# Navigation.net
KiCad netlist of a schematic drawn in Altium Designer
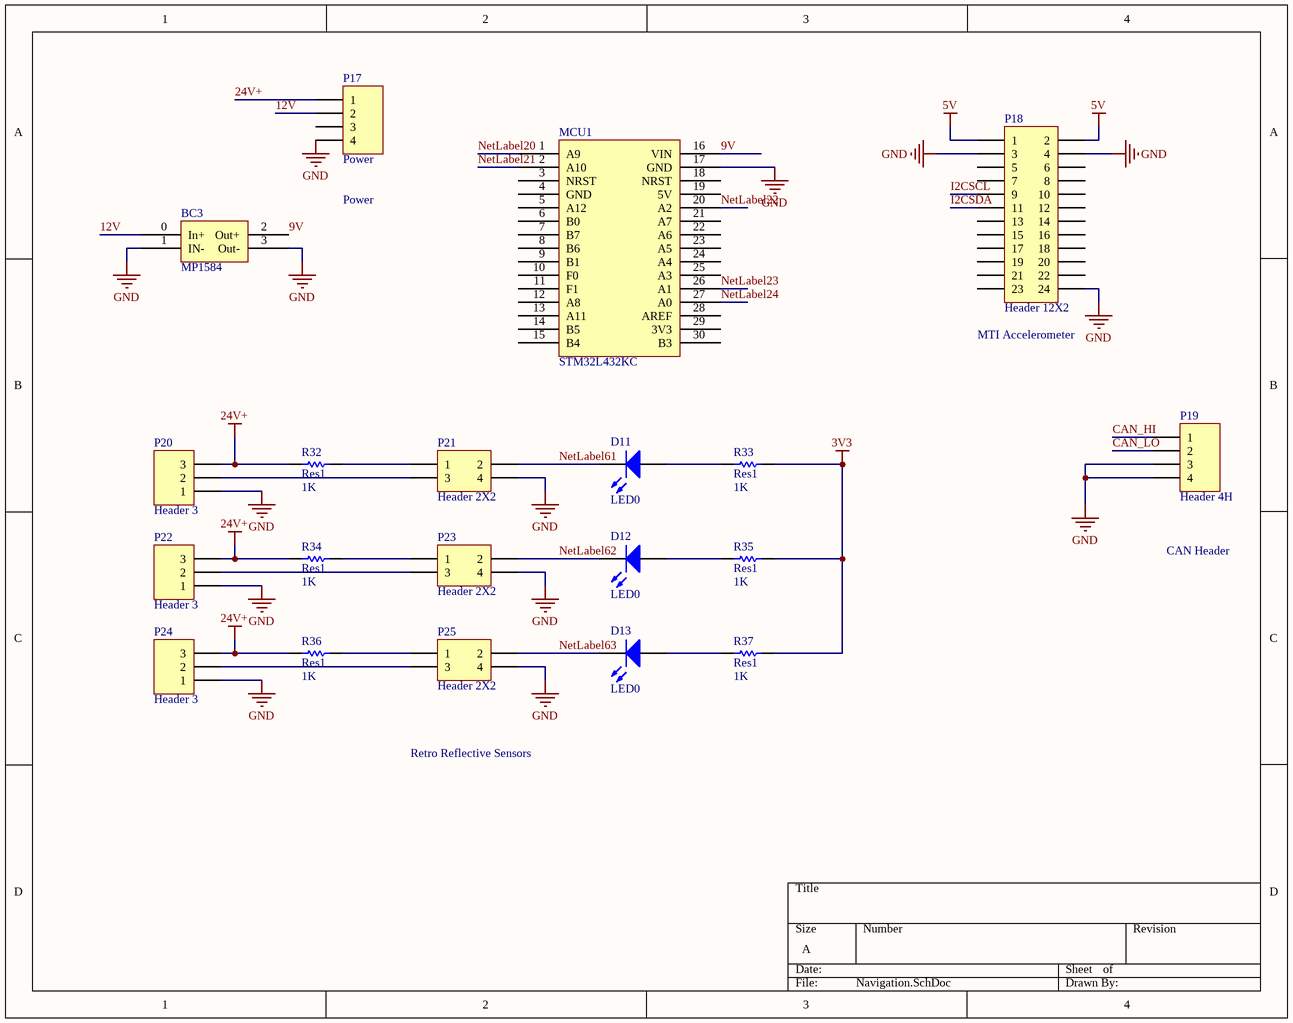
[diagram p0: Navigation.SchDoc]

(export (version "E")
  (design (tool "Eeschema 10.0.6"))
  (components
    (comp (ref "BC3") (value "MP1584") (libsource (lib "Pod3") (part "MP1584")))
    (comp (ref "D11")
      (value "LED0")
      (footprint "LED-0")
      (description "Typical INFRARED GaAs LED")
      (fields (field (name "PUBLISHER") "Altium Limited"))
      (libsource (lib "Miscellaneous Devices") (part "LED0"))
    )
    (comp (ref "D12")
      (value "LED0")
      (footprint "LED-0")
      (description "Typical INFRARED GaAs LED")
      (fields (field (name "PUBLISHER") "Altium Limited"))
      (libsource (lib "Miscellaneous Devices") (part "LED0"))
    )
    (comp (ref "D13")
      (value "LED0")
      (footprint "LED-0")
      (description "Typical INFRARED GaAs LED")
      (fields (field (name "PUBLISHER") "Altium Limited"))
      (libsource (lib "Miscellaneous Devices") (part "LED0"))
    )
    (comp (ref "MCU1") (value "STM32L432KC") (libsource (lib "Pod3") (part "STMF303K8")))
    (comp (ref "P17")
      (value "Power")
      (footprint "HDR1X4")
      (description "Header, 4-Pin")
      (fields (field (name "PUBLISHER") "Altium Limited"))
      (libsource (lib "Miscellaneous Connectors") (part "Header 4"))
    )
    (comp (ref "P18")
      (value "Header 12X2")
      (footprint "HDR2X12")
      (description "Header, 12-Pin, Dual row")
      (fields (field (name "PUBLISHER") "Altium Limited"))
      (libsource (lib "Miscellaneous Connectors") (part "Header 12X2"))
    )
    (comp (ref "P19")
      (value "Header 4H")
      (footprint "HDR1X4H")
      (description "Header, 4-Pin, Right Angle")
      (fields (field (name "PUBLISHER") "Altium Limited"))
      (libsource (lib "Miscellaneous Connectors") (part "Header 4H"))
    )
    (comp (ref "P20")
      (value "Header 3")
      (footprint "HDR1X3")
      (description "Header, 3-Pin")
      (fields (field (name "PUBLISHER") "Altium Limited"))
      (libsource (lib "Miscellaneous Connectors") (part "Header 3"))
    )
    (comp (ref "P21")
      (value "Header 2X2")
      (footprint "HDR2X2")
      (description "Header, 2-Pin, Dual row")
      (fields (field (name "PUBLISHER") "Altium Limited"))
      (libsource (lib "Miscellaneous Connectors") (part "Header 2X2"))
    )
    (comp (ref "P22")
      (value "Header 3")
      (footprint "HDR1X3")
      (description "Header, 3-Pin")
      (fields (field (name "PUBLISHER") "Altium Limited"))
      (libsource (lib "Miscellaneous Connectors") (part "Header 3"))
    )
    (comp (ref "P23")
      (value "Header 2X2")
      (footprint "HDR2X2")
      (description "Header, 2-Pin, Dual row")
      (fields (field (name "PUBLISHER") "Altium Limited"))
      (libsource (lib "Miscellaneous Connectors") (part "Header 2X2"))
    )
    (comp (ref "P24")
      (value "Header 3")
      (footprint "HDR1X3")
      (description "Header, 3-Pin")
      (fields (field (name "PUBLISHER") "Altium Limited"))
      (libsource (lib "Miscellaneous Connectors") (part "Header 3"))
    )
    (comp (ref "P25")
      (value "Header 2X2")
      (footprint "HDR2X2")
      (description "Header, 2-Pin, Dual row")
      (fields (field (name "PUBLISHER") "Altium Limited"))
      (libsource (lib "Miscellaneous Connectors") (part "Header 2X2"))
    )
    (comp (ref "R32")
      (value "Res1")
      (footprint "AXIAL-0.3")
      (description "Resistor")
      (fields (field (name "ALTIUM_VALUE") "1K") (field (name "PUBLISHER") "Altium Limited"))
      (libsource (lib "Miscellaneous Devices") (part "Res1"))
    )
    (comp (ref "R33")
      (value "Res1")
      (footprint "AXIAL-0.3")
      (description "Resistor")
      (fields (field (name "ALTIUM_VALUE") "1K") (field (name "PUBLISHER") "Altium Limited"))
      (libsource (lib "Miscellaneous Devices") (part "Res1"))
    )
    (comp (ref "R34")
      (value "Res1")
      (footprint "AXIAL-0.3")
      (description "Resistor")
      (fields (field (name "ALTIUM_VALUE") "1K") (field (name "PUBLISHER") "Altium Limited"))
      (libsource (lib "Miscellaneous Devices") (part "Res1"))
    )
    (comp (ref "R35")
      (value "Res1")
      (footprint "AXIAL-0.3")
      (description "Resistor")
      (fields (field (name "ALTIUM_VALUE") "1K") (field (name "PUBLISHER") "Altium Limited"))
      (libsource (lib "Miscellaneous Devices") (part "Res1"))
    )
    (comp (ref "R36")
      (value "Res1")
      (footprint "AXIAL-0.3")
      (description "Resistor")
      (fields (field (name "ALTIUM_VALUE") "1K") (field (name "PUBLISHER") "Altium Limited"))
      (libsource (lib "Miscellaneous Devices") (part "Res1"))
    )
    (comp (ref "R37")
      (value "Res1")
      (footprint "AXIAL-0.3")
      (description "Resistor")
      (fields (field (name "ALTIUM_VALUE") "1K") (field (name "PUBLISHER") "Altium Limited"))
      (libsource (lib "Miscellaneous Devices") (part "Res1"))
    )
  )
  (nets
    (net (code "1") (name "/9V") (class "Default")
      (node (ref "BC3") (pin "2") (pinfunction "Out+_2") (pintype "passive"))
      (node (ref "MCU1") (pin "16") (pinfunction "VIN_16") (pintype "passive"))
    )
    (net (code "2") (name "/12V") (class "Default")
      (node (ref "BC3") (pin "0") (pinfunction "In+_0") (pintype "passive"))
      (node (ref "P17") (pin "2") (pinfunction "2_2") (pintype "passive"))
    )
    (net (code "3") (name "/CAN_HI") (class "Default")
      (node (ref "P19") (pin "1") (pinfunction "1_1") (pintype "passive"))
    )
    (net (code "4") (name "/CAN_LO") (class "Default")
      (node (ref "P19") (pin "2") (pinfunction "2_2") (pintype "passive"))
    )
    (net (code "5") (name "/I2CSCL") (class "Default")
      (node (ref "P18") (pin "9") (pinfunction "9_9") (pintype "passive"))
    )
    (net (code "6") (name "/I2CSDA") (class "Default")
      (node (ref "P18") (pin "11") (pinfunction "11_11") (pintype "passive"))
    )
    (net (code "7") (name "/NetLabel20") (class "Default")
      (node (ref "MCU1") (pin "1") (pinfunction "A9_1") (pintype "passive"))
    )
    (net (code "8") (name "/NetLabel21") (class "Default")
      (node (ref "MCU1") (pin "2") (pinfunction "A10_2") (pintype "passive"))
    )
    (net (code "9") (name "/NetLabel22") (class "Default")
      (node (ref "MCU1") (pin "20") (pinfunction "A2_20") (pintype "passive"))
    )
    (net (code "10") (name "/NetLabel23") (class "Default")
      (node (ref "MCU1") (pin "26") (pinfunction "A1_26") (pintype "passive"))
    )
    (net (code "11") (name "/NetLabel24") (class "Default")
      (node (ref "MCU1") (pin "27") (pinfunction "A0_27") (pintype "passive"))
    )
    (net (code "12") (name "/NetLabel61") (class "Default")
      (node (ref "D11") (pin "2") (pinfunction "K_2") (pintype "passive"))
      (node (ref "P21") (pin "2") (pinfunction "2_2") (pintype "passive"))
    )
    (net (code "13") (name "/NetLabel62") (class "Default")
      (node (ref "D12") (pin "2") (pinfunction "K_2") (pintype "passive"))
      (node (ref "P23") (pin "2") (pinfunction "2_2") (pintype "passive"))
    )
    (net (code "14") (name "/NetLabel63") (class "Default")
      (node (ref "D13") (pin "2") (pinfunction "K_2") (pintype "passive"))
      (node (ref "P25") (pin "2") (pinfunction "2_2") (pintype "passive"))
    )
    (net (code "15") (name "3V3") (class "Default")
      (node (ref "R33") (pin "2") (pinfunction "2_2") (pintype "passive"))
      (node (ref "R35") (pin "2") (pinfunction "2_2") (pintype "passive"))
      (node (ref "R37") (pin "2") (pinfunction "2_2") (pintype "passive"))
    )
    (net (code "16") (name "5V") (class "Default")
      (node (ref "P18") (pin "1") (pinfunction "1_1") (pintype "passive"))
      (node (ref "P18") (pin "2") (pinfunction "2_2") (pintype "passive"))
    )
    (net (code "17") (name "24V+") (class "Default")
      (node (ref "P17") (pin "1") (pinfunction "1_1") (pintype "passive"))
      (node (ref "P20") (pin "3") (pinfunction "3_3") (pintype "passive"))
      (node (ref "P22") (pin "3") (pinfunction "3_3") (pintype "passive"))
      (node (ref "P24") (pin "3") (pinfunction "3_3") (pintype "passive"))
      (node (ref "R32") (pin "1") (pinfunction "1_1") (pintype "passive"))
      (node (ref "R34") (pin "1") (pinfunction "1_1") (pintype "passive"))
      (node (ref "R36") (pin "1") (pinfunction "1_1") (pintype "passive"))
    )
    (net (code "18") (name "GND") (class "Default")
      (node (ref "BC3") (pin "1") (pinfunction "IN-_1") (pintype "passive"))
      (node (ref "BC3") (pin "3") (pinfunction "Out-_3") (pintype "passive"))
      (node (ref "MCU1") (pin "17") (pinfunction "GND_17") (pintype "passive"))
      (node (ref "P17") (pin "4") (pinfunction "4_4") (pintype "passive"))
      (node (ref "P18") (pin "24") (pinfunction "24_24") (pintype "passive"))
      (node (ref "P18") (pin "3") (pinfunction "3_3") (pintype "passive"))
      (node (ref "P18") (pin "4") (pinfunction "4_4") (pintype "passive"))
      (node (ref "P19") (pin "3") (pinfunction "3_3") (pintype "passive"))
      (node (ref "P19") (pin "4") (pinfunction "4_4") (pintype "passive"))
      (node (ref "P20") (pin "1") (pinfunction "1_1") (pintype "passive"))
      (node (ref "P21") (pin "4") (pinfunction "4_4") (pintype "passive"))
      (node (ref "P22") (pin "1") (pinfunction "1_1") (pintype "passive"))
      (node (ref "P23") (pin "4") (pinfunction "4_4") (pintype "passive"))
      (node (ref "P24") (pin "1") (pinfunction "1_1") (pintype "passive"))
      (node (ref "P25") (pin "4") (pinfunction "4_4") (pintype "passive"))
    )
    (net (code "19") (name "Net-(D11-A)") (class "Default")
      (node (ref "D11") (pin "1") (pinfunction "A_1") (pintype "passive"))
      (node (ref "R33") (pin "1") (pinfunction "1_1") (pintype "passive"))
    )
    (net (code "20") (name "Net-(D12-A)") (class "Default")
      (node (ref "D12") (pin "1") (pinfunction "A_1") (pintype "passive"))
      (node (ref "R35") (pin "1") (pinfunction "1_1") (pintype "passive"))
    )
    (net (code "21") (name "Net-(D13-A)") (class "Default")
      (node (ref "D13") (pin "1") (pinfunction "A_1") (pintype "passive"))
      (node (ref "R37") (pin "1") (pinfunction "1_1") (pintype "passive"))
    )
    (net (code "22") (name "Net-(P20-Pad2)") (class "Default")
      (node (ref "P20") (pin "2") (pinfunction "2_2") (pintype "passive"))
      (node (ref "P21") (pin "3") (pinfunction "3_3") (pintype "passive"))
    )
    (net (code "23") (name "Net-(P21-Pad1)") (class "Default")
      (node (ref "P21") (pin "1") (pinfunction "1_1") (pintype "passive"))
      (node (ref "R32") (pin "2") (pinfunction "2_2") (pintype "passive"))
    )
    (net (code "24") (name "Net-(P22-Pad2)") (class "Default")
      (node (ref "P22") (pin "2") (pinfunction "2_2") (pintype "passive"))
      (node (ref "P23") (pin "3") (pinfunction "3_3") (pintype "passive"))
    )
    (net (code "25") (name "Net-(P23-Pad1)") (class "Default")
      (node (ref "P23") (pin "1") (pinfunction "1_1") (pintype "passive"))
      (node (ref "R34") (pin "2") (pinfunction "2_2") (pintype "passive"))
    )
    (net (code "26") (name "Net-(P24-Pad2)") (class "Default")
      (node (ref "P24") (pin "2") (pinfunction "2_2") (pintype "passive"))
      (node (ref "P25") (pin "3") (pinfunction "3_3") (pintype "passive"))
    )
    (net (code "27") (name "Net-(P25-Pad1)") (class "Default")
      (node (ref "P25") (pin "1") (pinfunction "1_1") (pintype "passive"))
      (node (ref "R36") (pin "2") (pinfunction "2_2") (pintype "passive"))
    )
    (net (code "28") (name "unconnected-(MCU1-3V3-Pad29)") (class "Default")
      (node (ref "MCU1") (pin "29") (pinfunction "3V3_29") (pintype "passive"))
    )
    (net (code "29") (name "unconnected-(MCU1-5V-Pad19)") (class "Default")
      (node (ref "MCU1") (pin "19") (pinfunction "5V_19") (pintype "passive"))
    )
    (net (code "30") (name "unconnected-(MCU1-A3-Pad25)") (class "Default")
      (node (ref "MCU1") (pin "25") (pinfunction "A3_25") (pintype "passive"))
    )
    (net (code "31") (name "unconnected-(MCU1-A4-Pad24)") (class "Default")
      (node (ref "MCU1") (pin "24") (pinfunction "A4_24") (pintype "passive"))
    )
    (net (code "32") (name "unconnected-(MCU1-A5-Pad23)") (class "Default")
      (node (ref "MCU1") (pin "23") (pinfunction "A5_23") (pintype "passive"))
    )
    (net (code "33") (name "unconnected-(MCU1-A6-Pad22)") (class "Default")
      (node (ref "MCU1") (pin "22") (pinfunction "A6_22") (pintype "passive"))
    )
    (net (code "34") (name "unconnected-(MCU1-A7-Pad21)") (class "Default")
      (node (ref "MCU1") (pin "21") (pinfunction "A7_21") (pintype "passive"))
    )
    (net (code "35") (name "unconnected-(MCU1-A8-Pad12)") (class "Default")
      (node (ref "MCU1") (pin "12") (pinfunction "A8_12") (pintype "passive"))
    )
    (net (code "36") (name "unconnected-(MCU1-A11-Pad13)") (class "Default")
      (node (ref "MCU1") (pin "13") (pinfunction "A11_13") (pintype "passive"))
    )
    (net (code "37") (name "unconnected-(MCU1-A12-Pad5)") (class "Default")
      (node (ref "MCU1") (pin "5") (pinfunction "A12_5") (pintype "passive"))
    )
    (net (code "38") (name "unconnected-(MCU1-AREF-Pad28)") (class "Default")
      (node (ref "MCU1") (pin "28") (pinfunction "AREF_28") (pintype "passive"))
    )
    (net (code "39") (name "unconnected-(MCU1-B0-Pad6)") (class "Default")
      (node (ref "MCU1") (pin "6") (pinfunction "B0_6") (pintype "passive"))
    )
    (net (code "40") (name "unconnected-(MCU1-B1-Pad9)") (class "Default")
      (node (ref "MCU1") (pin "9") (pinfunction "B1_9") (pintype "passive"))
    )
    (net (code "41") (name "unconnected-(MCU1-B3-Pad30)") (class "Default")
      (node (ref "MCU1") (pin "30") (pinfunction "B3_30") (pintype "passive"))
    )
    (net (code "42") (name "unconnected-(MCU1-B4-Pad15)") (class "Default")
      (node (ref "MCU1") (pin "15") (pinfunction "B4_15") (pintype "passive"))
    )
    (net (code "43") (name "unconnected-(MCU1-B5-Pad14)") (class "Default")
      (node (ref "MCU1") (pin "14") (pinfunction "B5_14") (pintype "passive"))
    )
    (net (code "44") (name "unconnected-(MCU1-B6-Pad8)") (class "Default")
      (node (ref "MCU1") (pin "8") (pinfunction "B6_8") (pintype "passive"))
    )
    (net (code "45") (name "unconnected-(MCU1-B7-Pad7)") (class "Default")
      (node (ref "MCU1") (pin "7") (pinfunction "B7_7") (pintype "passive"))
    )
    (net (code "46") (name "unconnected-(MCU1-F0-Pad10)") (class "Default")
      (node (ref "MCU1") (pin "10") (pinfunction "F0_10") (pintype "passive"))
    )
    (net (code "47") (name "unconnected-(MCU1-F1-Pad11)") (class "Default")
      (node (ref "MCU1") (pin "11") (pinfunction "F1_11") (pintype "passive"))
    )
    (net (code "48") (name "unconnected-(MCU1-GND-Pad4)") (class "Default")
      (node (ref "MCU1") (pin "4") (pinfunction "GND_4") (pintype "passive"))
    )
    (net (code "49") (name "unconnected-(MCU1-NRST-Pad3)") (class "Default")
      (node (ref "MCU1") (pin "3") (pinfunction "NRST_3") (pintype "passive"))
    )
    (net (code "50") (name "unconnected-(MCU1-NRST-Pad18)") (class "Default")
      (node (ref "MCU1") (pin "18") (pinfunction "NRST_18") (pintype "passive"))
    )
    (net (code "51") (name "unconnected-(P17-Pad3)") (class "Default")
      (node (ref "P17") (pin "3") (pinfunction "3_3") (pintype "passive"))
    )
    (net (code "52") (name "unconnected-(P18-Pad5)") (class "Default")
      (node (ref "P18") (pin "5") (pinfunction "5_5") (pintype "passive"))
    )
    (net (code "53") (name "unconnected-(P18-Pad6)") (class "Default")
      (node (ref "P18") (pin "6") (pinfunction "6_6") (pintype "passive"))
    )
    (net (code "54") (name "unconnected-(P18-Pad7)") (class "Default")
      (node (ref "P18") (pin "7") (pinfunction "7_7") (pintype "passive"))
    )
    (net (code "55") (name "unconnected-(P18-Pad8)") (class "Default")
      (node (ref "P18") (pin "8") (pinfunction "8_8") (pintype "passive"))
    )
    (net (code "56") (name "unconnected-(P18-Pad10)") (class "Default")
      (node (ref "P18") (pin "10") (pinfunction "10_10") (pintype "passive"))
    )
    (net (code "57") (name "unconnected-(P18-Pad12)") (class "Default")
      (node (ref "P18") (pin "12") (pinfunction "12_12") (pintype "passive"))
    )
    (net (code "58") (name "unconnected-(P18-Pad13)") (class "Default")
      (node (ref "P18") (pin "13") (pinfunction "13_13") (pintype "passive"))
    )
    (net (code "59") (name "unconnected-(P18-Pad14)") (class "Default")
      (node (ref "P18") (pin "14") (pinfunction "14_14") (pintype "passive"))
    )
    (net (code "60") (name "unconnected-(P18-Pad15)") (class "Default")
      (node (ref "P18") (pin "15") (pinfunction "15_15") (pintype "passive"))
    )
    (net (code "61") (name "unconnected-(P18-Pad16)") (class "Default")
      (node (ref "P18") (pin "16") (pinfunction "16_16") (pintype "passive"))
    )
    (net (code "62") (name "unconnected-(P18-Pad17)") (class "Default")
      (node (ref "P18") (pin "17") (pinfunction "17_17") (pintype "passive"))
    )
    (net (code "63") (name "unconnected-(P18-Pad18)") (class "Default")
      (node (ref "P18") (pin "18") (pinfunction "18_18") (pintype "passive"))
    )
    (net (code "64") (name "unconnected-(P18-Pad19)") (class "Default")
      (node (ref "P18") (pin "19") (pinfunction "19_19") (pintype "passive"))
    )
    (net (code "65") (name "unconnected-(P18-Pad20)") (class "Default")
      (node (ref "P18") (pin "20") (pinfunction "20_20") (pintype "passive"))
    )
    (net (code "66") (name "unconnected-(P18-Pad21)") (class "Default")
      (node (ref "P18") (pin "21") (pinfunction "21_21") (pintype "passive"))
    )
    (net (code "67") (name "unconnected-(P18-Pad22)") (class "Default")
      (node (ref "P18") (pin "22") (pinfunction "22_22") (pintype "passive"))
    )
    (net (code "68") (name "unconnected-(P18-Pad23)") (class "Default")
      (node (ref "P18") (pin "23") (pinfunction "23_23") (pintype "passive"))
    )
  )
)
